# mic_array.net
KiCad netlist of a schematic drawn in Altium Designer
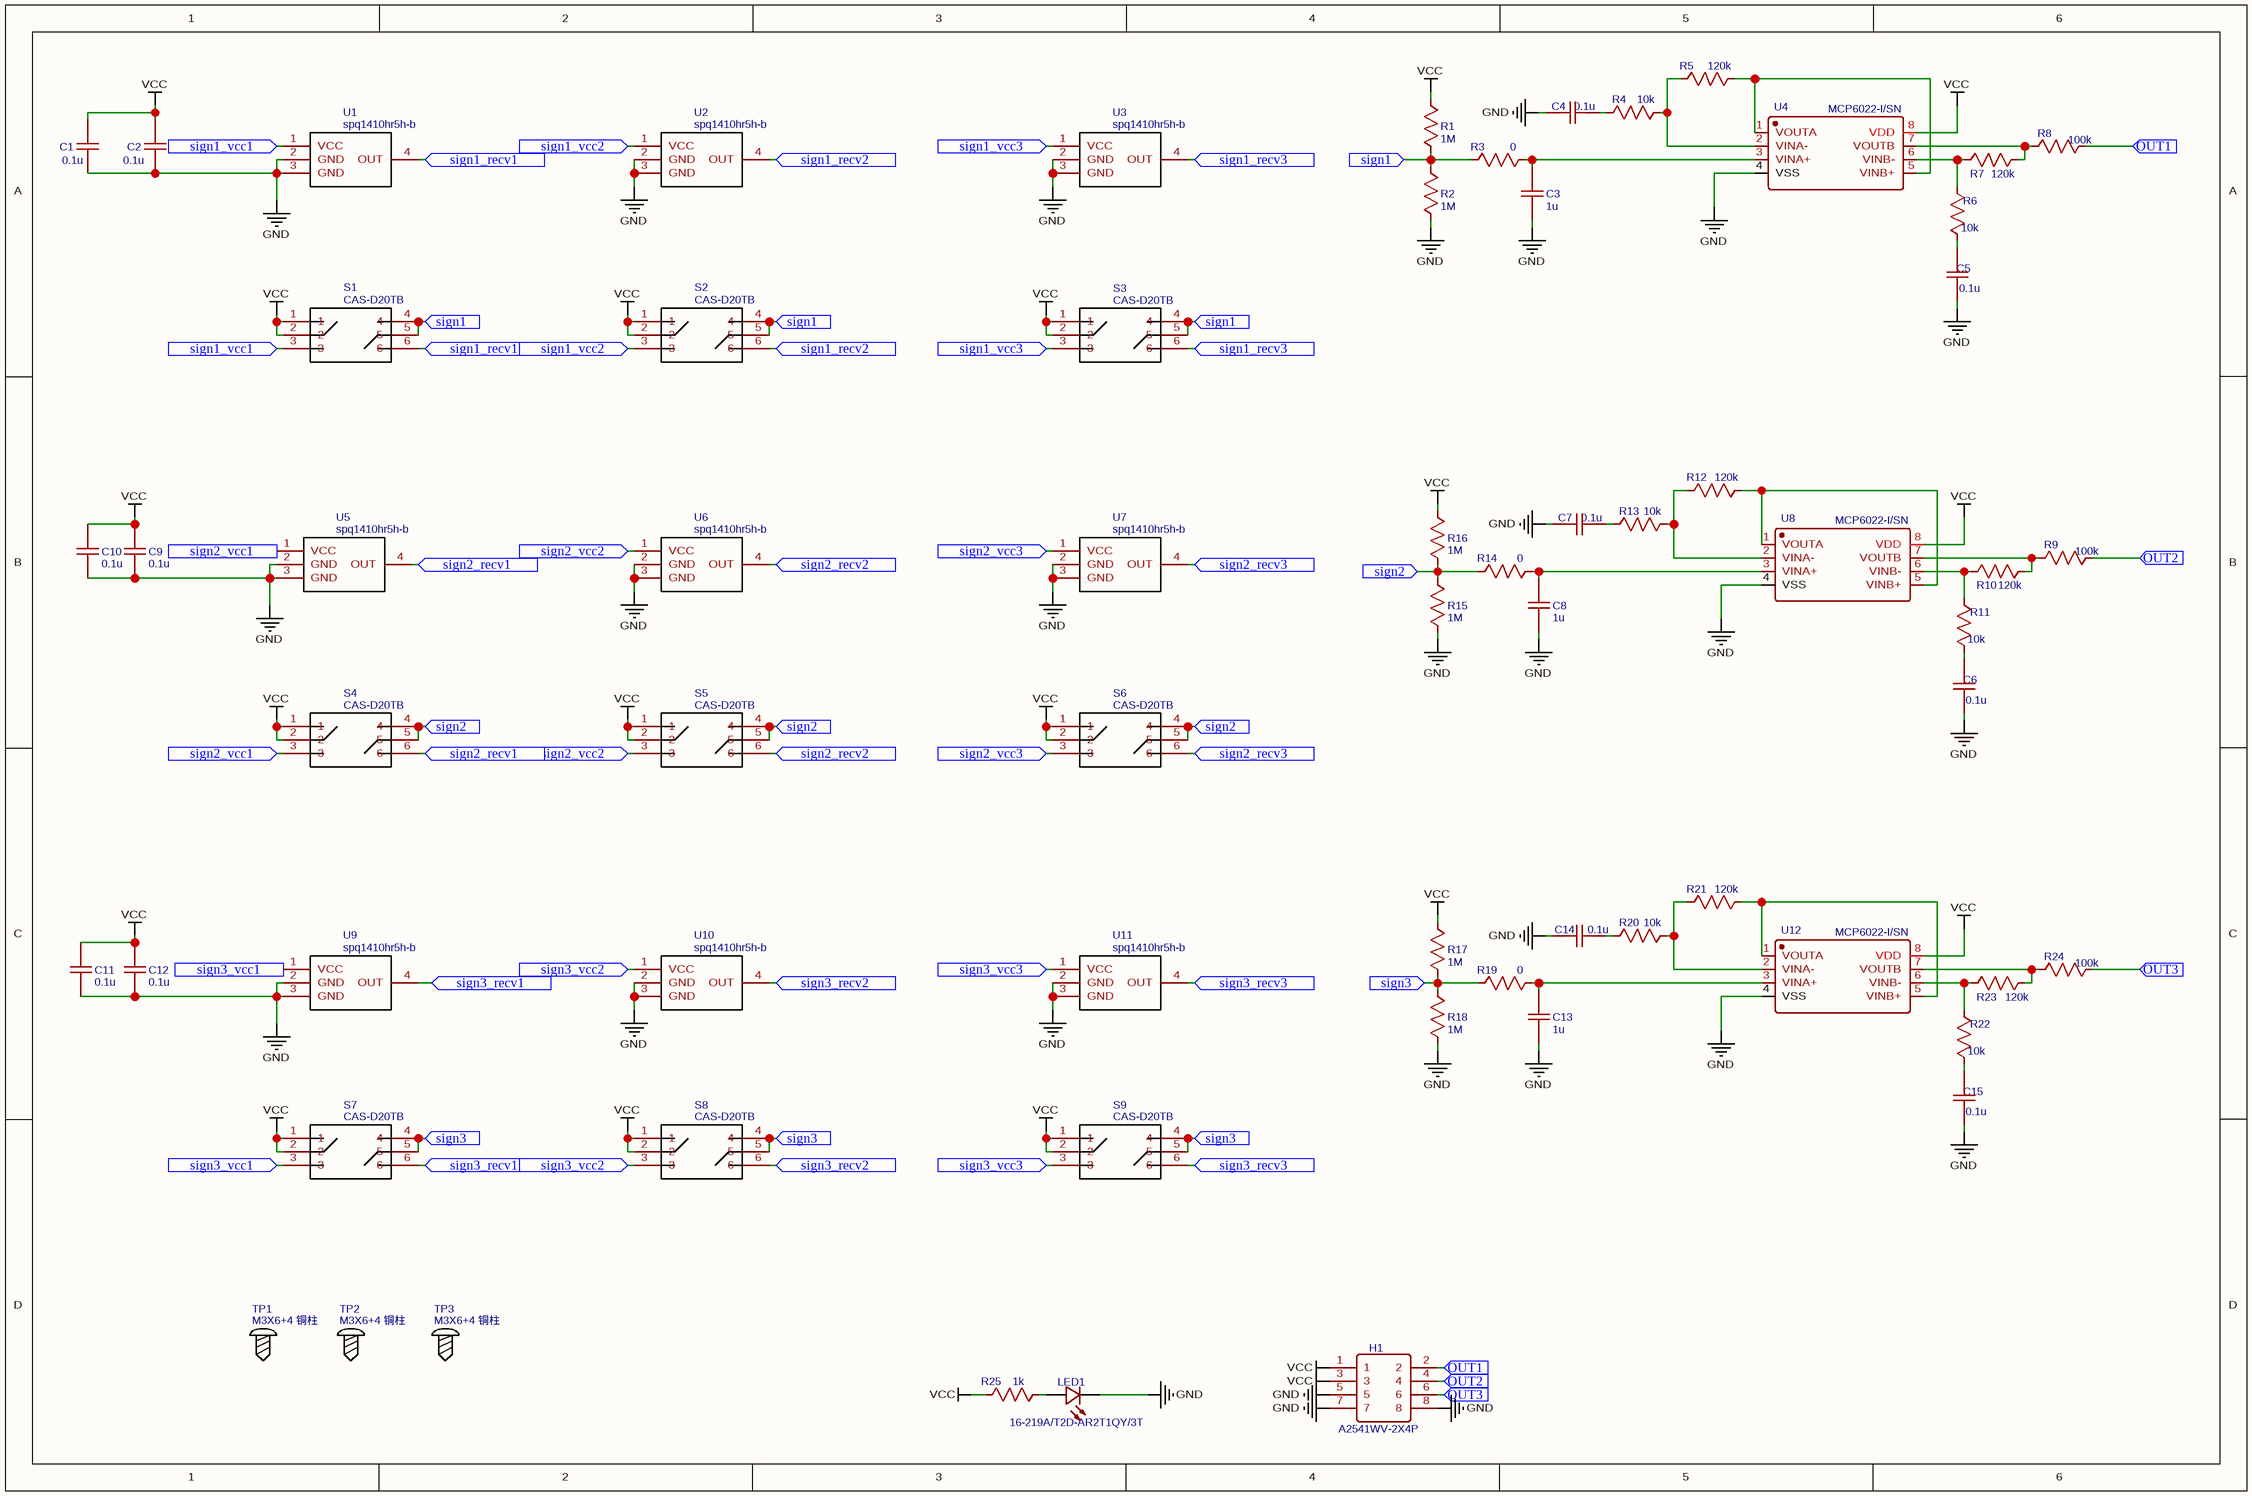
[diagram p0: mic_array.schdoc]

(export (version "E")
  (design (tool "Eeschema 10.0.6"))
  (components
    (comp (ref "C1")
      (value "0.1u")
      (fields (field (name "CONTRIBUTOR") "LCEDA_Lib"))
      (libsource (lib "altium-import") (part "root_1_0.1u_"))
    )
    (comp (ref "C2")
      (value "0.1u")
      (fields (field (name "CONTRIBUTOR") "LCEDA_Lib"))
      (libsource (lib "altium-import") (part "root_1_0.1u_"))
    )
    (comp (ref "C3")
      (value "1u")
      (fields (field (name "CONTRIBUTOR") "LCEDA_Lib"))
      (libsource (lib "altium-import") (part "root_1_1u_"))
    )
    (comp (ref "C4")
      (value "0.1u")
      (fields (field (name "CONTRIBUTOR") "LCEDA_Lib"))
      (libsource (lib "altium-import") (part "root_2_0.1u_"))
    )
    (comp (ref "C5")
      (value "0.1u")
      (fields (field (name "CONTRIBUTOR") "LCEDA_Lib"))
      (libsource (lib "altium-import") (part "root_1_0.1u_"))
    )
    (comp (ref "C6")
      (value "0.1u")
      (fields (field (name "CONTRIBUTOR") "LCEDA_Lib"))
      (libsource (lib "altium-import") (part "root_1_0.1u_"))
    )
    (comp (ref "C7")
      (value "0.1u")
      (fields (field (name "CONTRIBUTOR") "LCEDA_Lib"))
      (libsource (lib "altium-import") (part "root_2_0.1u_"))
    )
    (comp (ref "C8")
      (value "1u")
      (fields (field (name "CONTRIBUTOR") "LCEDA_Lib"))
      (libsource (lib "altium-import") (part "root_1_1u_"))
    )
    (comp (ref "C9")
      (value "0.1u")
      (fields (field (name "CONTRIBUTOR") "LCEDA_Lib"))
      (libsource (lib "altium-import") (part "root_1_0.1u_"))
    )
    (comp (ref "C10")
      (value "0.1u")
      (fields (field (name "CONTRIBUTOR") "LCEDA_Lib"))
      (libsource (lib "altium-import") (part "root_1_0.1u_"))
    )
    (comp (ref "C11")
      (value "0.1u")
      (fields (field (name "CONTRIBUTOR") "LCEDA_Lib"))
      (libsource (lib "altium-import") (part "root_1_0.1u_"))
    )
    (comp (ref "C12")
      (value "0.1u")
      (fields (field (name "CONTRIBUTOR") "LCEDA_Lib"))
      (libsource (lib "altium-import") (part "root_1_0.1u_"))
    )
    (comp (ref "C13")
      (value "1u")
      (fields (field (name "CONTRIBUTOR") "LCEDA_Lib"))
      (libsource (lib "altium-import") (part "root_1_1u_"))
    )
    (comp (ref "C14")
      (value "0.1u")
      (fields (field (name "CONTRIBUTOR") "LCEDA_Lib"))
      (libsource (lib "altium-import") (part "root_2_0.1u_"))
    )
    (comp (ref "C15")
      (value "0.1u")
      (fields (field (name "CONTRIBUTOR") "LCEDA_Lib"))
      (libsource (lib "altium-import") (part "root_1_0.1u_"))
    )
    (comp (ref "H1")
      (value "A2541WV-2X4P")
      (fields
        (field (name "BOM_SUPPLIER PART") "C225519")
        (field (name "BOM_MANUFACTURER PART") "A2541WV-2x4P")
        (field (name "CONTRIBUTOR") "LCSC")
      )
      (libsource (lib "altium-import") (part "root_0_A2541WV-2X4P_"))
    )
    (comp (ref "LED1")
      (value "16-219A/T2D-AR2T1QY/3T")
      (fields (field (name "BOM_SUPPLIER PART") "C74342"))
      (libsource (lib "altium-import") (part "root_2_16-219A/T2D-AR2T1QY/3T_"))
    )
    (comp (ref "R1")
      (value "1M")
      (fields (field (name "CONTRIBUTOR") "LCEDA_Lib"))
      (libsource (lib "altium-import") (part "root_1_1M_"))
    )
    (comp (ref "R2")
      (value "1M")
      (fields (field (name "CONTRIBUTOR") "LCEDA_Lib"))
      (libsource (lib "altium-import") (part "root_1_1M_"))
    )
    (comp (ref "R3")
      (value "0")
      (fields (field (name "CONTRIBUTOR") "LCEDA_Lib"))
      (libsource (lib "altium-import") (part "root_2_0_"))
    )
    (comp (ref "R4")
      (value "10k")
      (fields (field (name "CONTRIBUTOR") "LCEDA_Lib"))
      (libsource (lib "altium-import") (part "root_2_10k_"))
    )
    (comp (ref "R5")
      (value "120k")
      (fields (field (name "CONTRIBUTOR") "LCEDA_Lib"))
      (libsource (lib "altium-import") (part "root_2_120k_"))
    )
    (comp (ref "R6")
      (value "10k")
      (fields (field (name "CONTRIBUTOR") "LCEDA_Lib"))
      (libsource (lib "altium-import") (part "root_1_10k_"))
    )
    (comp (ref "R7")
      (value "120k")
      (fields (field (name "CONTRIBUTOR") "LCEDA_Lib"))
      (libsource (lib "altium-import") (part "root_2_120k_"))
    )
    (comp (ref "R8")
      (value "100k")
      (fields (field (name "CONTRIBUTOR") "LCEDA_Lib"))
      (libsource (lib "altium-import") (part "root_2_100k_"))
    )
    (comp (ref "R9")
      (value "100k")
      (fields (field (name "CONTRIBUTOR") "LCEDA_Lib"))
      (libsource (lib "altium-import") (part "root_2_100k_"))
    )
    (comp (ref "R10")
      (value "120k")
      (fields (field (name "CONTRIBUTOR") "LCEDA_Lib"))
      (libsource (lib "altium-import") (part "root_2_120k_"))
    )
    (comp (ref "R11")
      (value "10k")
      (fields (field (name "CONTRIBUTOR") "LCEDA_Lib"))
      (libsource (lib "altium-import") (part "root_1_10k_"))
    )
    (comp (ref "R12")
      (value "120k")
      (fields (field (name "CONTRIBUTOR") "LCEDA_Lib"))
      (libsource (lib "altium-import") (part "root_2_120k_"))
    )
    (comp (ref "R13")
      (value "10k")
      (fields (field (name "CONTRIBUTOR") "LCEDA_Lib"))
      (libsource (lib "altium-import") (part "root_2_10k_"))
    )
    (comp (ref "R14")
      (value "0")
      (fields (field (name "CONTRIBUTOR") "LCEDA_Lib"))
      (libsource (lib "altium-import") (part "root_2_0_"))
    )
    (comp (ref "R15")
      (value "1M")
      (fields (field (name "CONTRIBUTOR") "LCEDA_Lib"))
      (libsource (lib "altium-import") (part "root_1_1M_"))
    )
    (comp (ref "R16")
      (value "1M")
      (fields (field (name "CONTRIBUTOR") "LCEDA_Lib"))
      (libsource (lib "altium-import") (part "root_1_1M_"))
    )
    (comp (ref "R17")
      (value "1M")
      (fields (field (name "CONTRIBUTOR") "LCEDA_Lib"))
      (libsource (lib "altium-import") (part "root_1_1M_"))
    )
    (comp (ref "R18")
      (value "1M")
      (fields (field (name "CONTRIBUTOR") "LCEDA_Lib"))
      (libsource (lib "altium-import") (part "root_1_1M_"))
    )
    (comp (ref "R19")
      (value "0")
      (fields (field (name "CONTRIBUTOR") "LCEDA_Lib"))
      (libsource (lib "altium-import") (part "root_2_0_"))
    )
    (comp (ref "R20")
      (value "10k")
      (fields (field (name "CONTRIBUTOR") "LCEDA_Lib"))
      (libsource (lib "altium-import") (part "root_2_10k_"))
    )
    (comp (ref "R21")
      (value "120k")
      (fields (field (name "CONTRIBUTOR") "LCEDA_Lib"))
      (libsource (lib "altium-import") (part "root_2_120k_"))
    )
    (comp (ref "R22")
      (value "10k")
      (fields (field (name "CONTRIBUTOR") "LCEDA_Lib"))
      (libsource (lib "altium-import") (part "root_1_10k_"))
    )
    (comp (ref "R23")
      (value "120k")
      (fields (field (name "CONTRIBUTOR") "LCEDA_Lib"))
      (libsource (lib "altium-import") (part "root_2_120k_"))
    )
    (comp (ref "R24")
      (value "100k")
      (fields (field (name "CONTRIBUTOR") "LCEDA_Lib"))
      (libsource (lib "altium-import") (part "root_2_100k_"))
    )
    (comp (ref "R25")
      (value "1k")
      (fields (field (name "CONTRIBUTOR") "LCEDA_Lib"))
      (libsource (lib "altium-import") (part "root_0_1k_"))
    )
    (comp (ref "S1")
      (value "CAS-D20TB")
      (fields (field (name "CONTRIBUTOR") "iceeeewoo"))
      (libsource (lib "altium-import") (part "root_0_CAS-D20TB_"))
    )
    (comp (ref "S2")
      (value "CAS-D20TB")
      (fields (field (name "CONTRIBUTOR") "iceeeewoo"))
      (libsource (lib "altium-import") (part "root_0_CAS-D20TB_"))
    )
    (comp (ref "S3")
      (value "CAS-D20TB")
      (fields (field (name "CONTRIBUTOR") "iceeeewoo"))
      (libsource (lib "altium-import") (part "root_0_CAS-D20TB_"))
    )
    (comp (ref "S4")
      (value "CAS-D20TB")
      (fields (field (name "CONTRIBUTOR") "iceeeewoo"))
      (libsource (lib "altium-import") (part "root_0_CAS-D20TB_"))
    )
    (comp (ref "S5")
      (value "CAS-D20TB")
      (fields (field (name "CONTRIBUTOR") "iceeeewoo"))
      (libsource (lib "altium-import") (part "root_0_CAS-D20TB_"))
    )
    (comp (ref "S6")
      (value "CAS-D20TB")
      (fields (field (name "CONTRIBUTOR") "iceeeewoo"))
      (libsource (lib "altium-import") (part "root_0_CAS-D20TB_"))
    )
    (comp (ref "S7")
      (value "CAS-D20TB")
      (fields (field (name "CONTRIBUTOR") "iceeeewoo"))
      (libsource (lib "altium-import") (part "root_0_CAS-D20TB_"))
    )
    (comp (ref "S8")
      (value "CAS-D20TB")
      (fields (field (name "CONTRIBUTOR") "iceeeewoo"))
      (libsource (lib "altium-import") (part "root_0_CAS-D20TB_"))
    )
    (comp (ref "S9")
      (value "CAS-D20TB")
      (fields (field (name "CONTRIBUTOR") "iceeeewoo"))
      (libsource (lib "altium-import") (part "root_0_CAS-D20TB_"))
    )
    (comp (ref "TP1")
      (value "M3X6+4 铜柱")
      (fields (field (name "BOM_SUPPLIER PART") "C551320") (field (name "CONTRIBUTOR") "eda2022"))
      (libsource (lib "altium-import") (part "root_0_M3X6+4 铜柱_"))
    )
    (comp (ref "TP2")
      (value "M3X6+4 铜柱")
      (fields (field (name "BOM_SUPPLIER PART") "C551320") (field (name "CONTRIBUTOR") "eda2022"))
      (libsource (lib "altium-import") (part "root_0_M3X6+4 铜柱_"))
    )
    (comp (ref "TP3")
      (value "M3X6+4 铜柱")
      (fields (field (name "BOM_SUPPLIER PART") "C551320") (field (name "CONTRIBUTOR") "eda2022"))
      (libsource (lib "altium-import") (part "root_0_M3X6+4 铜柱_"))
    )
    (comp (ref "U1")
      (value "spq1410hr5h-b")
      (fields (field (name "CONTRIBUTOR") "Iceeeewoo"))
      (libsource (lib "altium-import") (part "root_0_spq1410hr5h-b_"))
    )
    (comp (ref "U2")
      (value "spq1410hr5h-b")
      (fields (field (name "CONTRIBUTOR") "Iceeeewoo"))
      (libsource (lib "altium-import") (part "root_0_spq1410hr5h-b_"))
    )
    (comp (ref "U3")
      (value "spq1410hr5h-b")
      (fields (field (name "CONTRIBUTOR") "Iceeeewoo"))
      (libsource (lib "altium-import") (part "root_0_spq1410hr5h-b_"))
    )
    (comp (ref "U4")
      (value "MCP6022-I/SN")
      (fields (field (name "BOM_SUPPLIER PART") "C34047"))
      (libsource (lib "altium-import") (part "root_0_MCP6022-I/SN_"))
    )
    (comp (ref "U5")
      (value "spq1410hr5h-b")
      (fields (field (name "CONTRIBUTOR") "Iceeeewoo"))
      (libsource (lib "altium-import") (part "root_0_spq1410hr5h-b_"))
    )
    (comp (ref "U6")
      (value "spq1410hr5h-b")
      (fields (field (name "CONTRIBUTOR") "Iceeeewoo"))
      (libsource (lib "altium-import") (part "root_0_spq1410hr5h-b_"))
    )
    (comp (ref "U7")
      (value "spq1410hr5h-b")
      (fields (field (name "CONTRIBUTOR") "Iceeeewoo"))
      (libsource (lib "altium-import") (part "root_0_spq1410hr5h-b_"))
    )
    (comp (ref "U8")
      (value "MCP6022-I/SN")
      (fields (field (name "BOM_SUPPLIER PART") "C34047"))
      (libsource (lib "altium-import") (part "root_0_MCP6022-I/SN_"))
    )
    (comp (ref "U9")
      (value "spq1410hr5h-b")
      (fields (field (name "CONTRIBUTOR") "Iceeeewoo"))
      (libsource (lib "altium-import") (part "root_0_spq1410hr5h-b_"))
    )
    (comp (ref "U10")
      (value "spq1410hr5h-b")
      (fields (field (name "CONTRIBUTOR") "Iceeeewoo"))
      (libsource (lib "altium-import") (part "root_0_spq1410hr5h-b_"))
    )
    (comp (ref "U11")
      (value "spq1410hr5h-b")
      (fields (field (name "CONTRIBUTOR") "Iceeeewoo"))
      (libsource (lib "altium-import") (part "root_0_spq1410hr5h-b_"))
    )
    (comp (ref "U12")
      (value "MCP6022-I/SN")
      (fields (field (name "BOM_SUPPLIER PART") "C34047"))
      (libsource (lib "altium-import") (part "root_0_MCP6022-I/SN_"))
    )
  )
  (nets
    (net (code "1") (name "/OUT1") (class "Default")
      (node (ref "H1") (pin "2") (pinfunction "2_2") (pintype "passive"))
      (node (ref "R8") (pin "1") (pinfunction "1_1") (pintype "passive"))
    )
    (net (code "2") (name "/OUT2") (class "Default")
      (node (ref "H1") (pin "4") (pinfunction "4_4") (pintype "passive"))
      (node (ref "R9") (pin "1") (pinfunction "1_1") (pintype "passive"))
    )
    (net (code "3") (name "/OUT3") (class "Default")
      (node (ref "H1") (pin "6") (pinfunction "6_6") (pintype "passive"))
      (node (ref "R24") (pin "1") (pinfunction "1_1") (pintype "passive"))
    )
    (net (code "4") (name "/sign1") (class "Default")
      (node (ref "R1") (pin "1") (pinfunction "1_1") (pintype "passive"))
      (node (ref "R2") (pin "2") (pinfunction "2_2") (pintype "passive"))
      (node (ref "R3") (pin "2") (pinfunction "2_2") (pintype "passive"))
      (node (ref "S1") (pin "4") (pinfunction "4_4") (pintype "passive"))
      (node (ref "S1") (pin "5") (pinfunction "5_5") (pintype "passive"))
      (node (ref "S2") (pin "4") (pinfunction "4_4") (pintype "passive"))
      (node (ref "S2") (pin "5") (pinfunction "5_5") (pintype "passive"))
      (node (ref "S3") (pin "4") (pinfunction "4_4") (pintype "passive"))
      (node (ref "S3") (pin "5") (pinfunction "5_5") (pintype "passive"))
    )
    (net (code "5") (name "/sign1_recv1") (class "Default")
      (node (ref "S1") (pin "6") (pinfunction "6_6") (pintype "passive"))
      (node (ref "U1") (pin "4") (pinfunction "OUT_4") (pintype "passive"))
    )
    (net (code "6") (name "/sign1_recv2") (class "Default")
      (node (ref "S2") (pin "6") (pinfunction "6_6") (pintype "passive"))
      (node (ref "U2") (pin "4") (pinfunction "OUT_4") (pintype "passive"))
    )
    (net (code "7") (name "/sign1_recv3") (class "Default")
      (node (ref "S3") (pin "6") (pinfunction "6_6") (pintype "passive"))
      (node (ref "U3") (pin "4") (pinfunction "OUT_4") (pintype "passive"))
    )
    (net (code "8") (name "/sign1_vcc1") (class "Default")
      (node (ref "S1") (pin "3") (pinfunction "3_3") (pintype "passive"))
      (node (ref "U1") (pin "1") (pinfunction "VCC_1") (pintype "passive"))
    )
    (net (code "9") (name "/sign1_vcc2") (class "Default")
      (node (ref "S2") (pin "3") (pinfunction "3_3") (pintype "passive"))
      (node (ref "U2") (pin "1") (pinfunction "VCC_1") (pintype "passive"))
    )
    (net (code "10") (name "/sign1_vcc3") (class "Default")
      (node (ref "S3") (pin "3") (pinfunction "3_3") (pintype "passive"))
      (node (ref "U3") (pin "1") (pinfunction "VCC_1") (pintype "passive"))
    )
    (net (code "11") (name "/sign2") (class "Default")
      (node (ref "R14") (pin "2") (pinfunction "2_2") (pintype "passive"))
      (node (ref "R15") (pin "2") (pinfunction "2_2") (pintype "passive"))
      (node (ref "R16") (pin "1") (pinfunction "1_1") (pintype "passive"))
      (node (ref "S4") (pin "4") (pinfunction "4_4") (pintype "passive"))
      (node (ref "S4") (pin "5") (pinfunction "5_5") (pintype "passive"))
      (node (ref "S5") (pin "4") (pinfunction "4_4") (pintype "passive"))
      (node (ref "S5") (pin "5") (pinfunction "5_5") (pintype "passive"))
      (node (ref "S6") (pin "4") (pinfunction "4_4") (pintype "passive"))
      (node (ref "S6") (pin "5") (pinfunction "5_5") (pintype "passive"))
    )
    (net (code "12") (name "/sign2_recv1") (class "Default")
      (node (ref "S4") (pin "6") (pinfunction "6_6") (pintype "passive"))
      (node (ref "U5") (pin "4") (pinfunction "OUT_4") (pintype "passive"))
    )
    (net (code "13") (name "/sign2_recv2") (class "Default")
      (node (ref "S5") (pin "6") (pinfunction "6_6") (pintype "passive"))
      (node (ref "U6") (pin "4") (pinfunction "OUT_4") (pintype "passive"))
    )
    (net (code "14") (name "/sign2_recv3") (class "Default")
      (node (ref "S6") (pin "6") (pinfunction "6_6") (pintype "passive"))
      (node (ref "U7") (pin "4") (pinfunction "OUT_4") (pintype "passive"))
    )
    (net (code "15") (name "/sign2_vcc1") (class "Default")
      (node (ref "S4") (pin "3") (pinfunction "3_3") (pintype "passive"))
      (node (ref "U5") (pin "1") (pinfunction "VCC_1") (pintype "passive"))
    )
    (net (code "16") (name "/sign2_vcc2") (class "Default")
      (node (ref "S5") (pin "3") (pinfunction "3_3") (pintype "passive"))
      (node (ref "U6") (pin "1") (pinfunction "VCC_1") (pintype "passive"))
    )
    (net (code "17") (name "/sign2_vcc3") (class "Default")
      (node (ref "S6") (pin "3") (pinfunction "3_3") (pintype "passive"))
      (node (ref "U7") (pin "1") (pinfunction "VCC_1") (pintype "passive"))
    )
    (net (code "18") (name "/sign3") (class "Default")
      (node (ref "R17") (pin "1") (pinfunction "1_1") (pintype "passive"))
      (node (ref "R18") (pin "2") (pinfunction "2_2") (pintype "passive"))
      (node (ref "R19") (pin "2") (pinfunction "2_2") (pintype "passive"))
      (node (ref "S7") (pin "4") (pinfunction "4_4") (pintype "passive"))
      (node (ref "S7") (pin "5") (pinfunction "5_5") (pintype "passive"))
      (node (ref "S8") (pin "4") (pinfunction "4_4") (pintype "passive"))
      (node (ref "S8") (pin "5") (pinfunction "5_5") (pintype "passive"))
      (node (ref "S9") (pin "4") (pinfunction "4_4") (pintype "passive"))
      (node (ref "S9") (pin "5") (pinfunction "5_5") (pintype "passive"))
    )
    (net (code "19") (name "/sign3_recv1") (class "Default")
      (node (ref "S7") (pin "6") (pinfunction "6_6") (pintype "passive"))
      (node (ref "U9") (pin "4") (pinfunction "OUT_4") (pintype "passive"))
    )
    (net (code "20") (name "/sign3_recv2") (class "Default")
      (node (ref "S8") (pin "6") (pinfunction "6_6") (pintype "passive"))
      (node (ref "U10") (pin "4") (pinfunction "OUT_4") (pintype "passive"))
    )
    (net (code "21") (name "/sign3_recv3") (class "Default")
      (node (ref "S9") (pin "6") (pinfunction "6_6") (pintype "passive"))
      (node (ref "U11") (pin "4") (pinfunction "OUT_4") (pintype "passive"))
    )
    (net (code "22") (name "/sign3_vcc1") (class "Default")
      (node (ref "S7") (pin "3") (pinfunction "3_3") (pintype "passive"))
      (node (ref "U9") (pin "1") (pinfunction "VCC_1") (pintype "passive"))
    )
    (net (code "23") (name "/sign3_vcc2") (class "Default")
      (node (ref "S8") (pin "3") (pinfunction "3_3") (pintype "passive"))
      (node (ref "U10") (pin "1") (pinfunction "VCC_1") (pintype "passive"))
    )
    (net (code "24") (name "/sign3_vcc3") (class "Default")
      (node (ref "S9") (pin "3") (pinfunction "3_3") (pintype "passive"))
      (node (ref "U11") (pin "1") (pinfunction "VCC_1") (pintype "passive"))
    )
    (net (code "25") (name "GND") (class "Default")
      (node (ref "C1") (pin "1") (pinfunction "1_1") (pintype "passive"))
      (node (ref "C10") (pin "1") (pinfunction "1_1") (pintype "passive"))
      (node (ref "C11") (pin "1") (pinfunction "1_1") (pintype "passive"))
      (node (ref "C12") (pin "1") (pinfunction "1_1") (pintype "passive"))
      (node (ref "C13") (pin "1") (pinfunction "1_1") (pintype "passive"))
      (node (ref "C14") (pin "2") (pinfunction "2_2") (pintype "passive"))
      (node (ref "C15") (pin "1") (pinfunction "1_1") (pintype "passive"))
      (node (ref "C2") (pin "1") (pinfunction "1_1") (pintype "passive"))
      (node (ref "C3") (pin "1") (pinfunction "1_1") (pintype "passive"))
      (node (ref "C4") (pin "2") (pinfunction "2_2") (pintype "passive"))
      (node (ref "C5") (pin "1") (pinfunction "1_1") (pintype "passive"))
      (node (ref "C6") (pin "1") (pinfunction "1_1") (pintype "passive"))
      (node (ref "C7") (pin "2") (pinfunction "2_2") (pintype "passive"))
      (node (ref "C8") (pin "1") (pinfunction "1_1") (pintype "passive"))
      (node (ref "C9") (pin "1") (pinfunction "1_1") (pintype "passive"))
      (node (ref "H1") (pin "5") (pinfunction "5_5") (pintype "passive"))
      (node (ref "H1") (pin "7") (pinfunction "7_7") (pintype "passive"))
      (node (ref "H1") (pin "8") (pinfunction "8_8") (pintype "passive"))
      (node (ref "LED1") (pin "1") (pinfunction "-_1") (pintype "passive"))
      (node (ref "R15") (pin "1") (pinfunction "1_1") (pintype "passive"))
      (node (ref "R18") (pin "1") (pinfunction "1_1") (pintype "passive"))
      (node (ref "R2") (pin "1") (pinfunction "1_1") (pintype "passive"))
      (node (ref "U1") (pin "2") (pinfunction "GND_2") (pintype "passive"))
      (node (ref "U1") (pin "3") (pinfunction "GND_3") (pintype "passive"))
      (node (ref "U10") (pin "2") (pinfunction "GND_2") (pintype "passive"))
      (node (ref "U10") (pin "3") (pinfunction "GND_3") (pintype "passive"))
      (node (ref "U11") (pin "2") (pinfunction "GND_2") (pintype "passive"))
      (node (ref "U11") (pin "3") (pinfunction "GND_3") (pintype "passive"))
      (node (ref "U12") (pin "4") (pinfunction "VSS_4") (pintype "passive"))
      (node (ref "U2") (pin "2") (pinfunction "GND_2") (pintype "passive"))
      (node (ref "U2") (pin "3") (pinfunction "GND_3") (pintype "passive"))
      (node (ref "U3") (pin "2") (pinfunction "GND_2") (pintype "passive"))
      (node (ref "U3") (pin "3") (pinfunction "GND_3") (pintype "passive"))
      (node (ref "U4") (pin "4") (pinfunction "VSS_4") (pintype "passive"))
      (node (ref "U5") (pin "2") (pinfunction "GND_2") (pintype "passive"))
      (node (ref "U5") (pin "3") (pinfunction "GND_3") (pintype "passive"))
      (node (ref "U6") (pin "2") (pinfunction "GND_2") (pintype "passive"))
      (node (ref "U6") (pin "3") (pinfunction "GND_3") (pintype "passive"))
      (node (ref "U7") (pin "2") (pinfunction "GND_2") (pintype "passive"))
      (node (ref "U7") (pin "3") (pinfunction "GND_3") (pintype "passive"))
      (node (ref "U8") (pin "4") (pinfunction "VSS_4") (pintype "passive"))
      (node (ref "U9") (pin "2") (pinfunction "GND_2") (pintype "passive"))
      (node (ref "U9") (pin "3") (pinfunction "GND_3") (pintype "passive"))
    )
    (net (code "26") (name "Net-(C4-Pad1)") (class "Default")
      (node (ref "C4") (pin "1") (pinfunction "1_1") (pintype "passive"))
      (node (ref "R4") (pin "2") (pinfunction "2_2") (pintype "passive"))
    )
    (net (code "27") (name "Net-(C5-Pad2)") (class "Default")
      (node (ref "C5") (pin "2") (pinfunction "2_2") (pintype "passive"))
      (node (ref "R6") (pin "1") (pinfunction "1_1") (pintype "passive"))
    )
    (net (code "28") (name "Net-(C6-Pad2)") (class "Default")
      (node (ref "C6") (pin "2") (pinfunction "2_2") (pintype "passive"))
      (node (ref "R11") (pin "1") (pinfunction "1_1") (pintype "passive"))
    )
    (net (code "29") (name "Net-(C7-Pad1)") (class "Default")
      (node (ref "C7") (pin "1") (pinfunction "1_1") (pintype "passive"))
      (node (ref "R13") (pin "2") (pinfunction "2_2") (pintype "passive"))
    )
    (net (code "30") (name "Net-(C14-Pad1)") (class "Default")
      (node (ref "C14") (pin "1") (pinfunction "1_1") (pintype "passive"))
      (node (ref "R20") (pin "2") (pinfunction "2_2") (pintype "passive"))
    )
    (net (code "31") (name "Net-(C15-Pad2)") (class "Default")
      (node (ref "C15") (pin "2") (pinfunction "2_2") (pintype "passive"))
      (node (ref "R22") (pin "1") (pinfunction "1_1") (pintype "passive"))
    )
    (net (code "32") (name "Net-(LED1-+)") (class "Default")
      (node (ref "LED1") (pin "2") (pinfunction "+_2") (pintype "passive"))
      (node (ref "R25") (pin "2") (pinfunction "2_2") (pintype "passive"))
    )
    (net (code "33") (name "Net-(U4-VINA+)") (class "Default")
      (node (ref "C3") (pin "2") (pinfunction "2_2") (pintype "passive"))
      (node (ref "R3") (pin "1") (pinfunction "1_1") (pintype "passive"))
      (node (ref "U4") (pin "3") (pinfunction "VINA+_3") (pintype "passive"))
    )
    (net (code "34") (name "Net-(U4-VINA-)") (class "Default")
      (node (ref "R4") (pin "1") (pinfunction "1_1") (pintype "passive"))
      (node (ref "R5") (pin "2") (pinfunction "2_2") (pintype "passive"))
      (node (ref "U4") (pin "2") (pinfunction "VINA-_2") (pintype "passive"))
    )
    (net (code "35") (name "Net-(U4-VINB+)") (class "Default")
      (node (ref "R5") (pin "1") (pinfunction "1_1") (pintype "passive"))
      (node (ref "U4") (pin "1") (pinfunction "VOUTA_1") (pintype "passive"))
      (node (ref "U4") (pin "5") (pinfunction "VINB+_5") (pintype "passive"))
    )
    (net (code "36") (name "Net-(U4-VINB-)") (class "Default")
      (node (ref "R6") (pin "2") (pinfunction "2_2") (pintype "passive"))
      (node (ref "R7") (pin "2") (pinfunction "2_2") (pintype "passive"))
      (node (ref "U4") (pin "6") (pinfunction "VINB-_6") (pintype "passive"))
    )
    (net (code "37") (name "Net-(U4-VOUTB)") (class "Default")
      (node (ref "R7") (pin "1") (pinfunction "1_1") (pintype "passive"))
      (node (ref "R8") (pin "2") (pinfunction "2_2") (pintype "passive"))
      (node (ref "U4") (pin "7") (pinfunction "VOUTB_7") (pintype "passive"))
    )
    (net (code "38") (name "Net-(U8-VINA+)") (class "Default")
      (node (ref "C8") (pin "2") (pinfunction "2_2") (pintype "passive"))
      (node (ref "R14") (pin "1") (pinfunction "1_1") (pintype "passive"))
      (node (ref "U8") (pin "3") (pinfunction "VINA+_3") (pintype "passive"))
    )
    (net (code "39") (name "Net-(U8-VINA-)") (class "Default")
      (node (ref "R12") (pin "2") (pinfunction "2_2") (pintype "passive"))
      (node (ref "R13") (pin "1") (pinfunction "1_1") (pintype "passive"))
      (node (ref "U8") (pin "2") (pinfunction "VINA-_2") (pintype "passive"))
    )
    (net (code "40") (name "Net-(U8-VINB+)") (class "Default")
      (node (ref "R12") (pin "1") (pinfunction "1_1") (pintype "passive"))
      (node (ref "U8") (pin "1") (pinfunction "VOUTA_1") (pintype "passive"))
      (node (ref "U8") (pin "5") (pinfunction "VINB+_5") (pintype "passive"))
    )
    (net (code "41") (name "Net-(U8-VINB-)") (class "Default")
      (node (ref "R10") (pin "2") (pinfunction "2_2") (pintype "passive"))
      (node (ref "R11") (pin "2") (pinfunction "2_2") (pintype "passive"))
      (node (ref "U8") (pin "6") (pinfunction "VINB-_6") (pintype "passive"))
    )
    (net (code "42") (name "Net-(U8-VOUTB)") (class "Default")
      (node (ref "R10") (pin "1") (pinfunction "1_1") (pintype "passive"))
      (node (ref "R9") (pin "2") (pinfunction "2_2") (pintype "passive"))
      (node (ref "U8") (pin "7") (pinfunction "VOUTB_7") (pintype "passive"))
    )
    (net (code "43") (name "Net-(U12-VINA+)") (class "Default")
      (node (ref "C13") (pin "2") (pinfunction "2_2") (pintype "passive"))
      (node (ref "R19") (pin "1") (pinfunction "1_1") (pintype "passive"))
      (node (ref "U12") (pin "3") (pinfunction "VINA+_3") (pintype "passive"))
    )
    (net (code "44") (name "Net-(U12-VINA-)") (class "Default")
      (node (ref "R20") (pin "1") (pinfunction "1_1") (pintype "passive"))
      (node (ref "R21") (pin "2") (pinfunction "2_2") (pintype "passive"))
      (node (ref "U12") (pin "2") (pinfunction "VINA-_2") (pintype "passive"))
    )
    (net (code "45") (name "Net-(U12-VINB+)") (class "Default")
      (node (ref "R21") (pin "1") (pinfunction "1_1") (pintype "passive"))
      (node (ref "U12") (pin "1") (pinfunction "VOUTA_1") (pintype "passive"))
      (node (ref "U12") (pin "5") (pinfunction "VINB+_5") (pintype "passive"))
    )
    (net (code "46") (name "Net-(U12-VINB-)") (class "Default")
      (node (ref "R22") (pin "2") (pinfunction "2_2") (pintype "passive"))
      (node (ref "R23") (pin "2") (pinfunction "2_2") (pintype "passive"))
      (node (ref "U12") (pin "6") (pinfunction "VINB-_6") (pintype "passive"))
    )
    (net (code "47") (name "Net-(U12-VOUTB)") (class "Default")
      (node (ref "R23") (pin "1") (pinfunction "1_1") (pintype "passive"))
      (node (ref "R24") (pin "2") (pinfunction "2_2") (pintype "passive"))
      (node (ref "U12") (pin "7") (pinfunction "VOUTB_7") (pintype "passive"))
    )
    (net (code "48") (name "VCC") (class "Default")
      (node (ref "C1") (pin "2") (pinfunction "2_2") (pintype "passive"))
      (node (ref "C10") (pin "2") (pinfunction "2_2") (pintype "passive"))
      (node (ref "C11") (pin "2") (pinfunction "2_2") (pintype "passive"))
      (node (ref "C12") (pin "2") (pinfunction "2_2") (pintype "passive"))
      (node (ref "C2") (pin "2") (pinfunction "2_2") (pintype "passive"))
      (node (ref "C9") (pin "2") (pinfunction "2_2") (pintype "passive"))
      (node (ref "H1") (pin "1") (pinfunction "1_1") (pintype "passive"))
      (node (ref "H1") (pin "3") (pinfunction "3_3") (pintype "passive"))
      (node (ref "R1") (pin "2") (pinfunction "2_2") (pintype "passive"))
      (node (ref "R16") (pin "2") (pinfunction "2_2") (pintype "passive"))
      (node (ref "R17") (pin "2") (pinfunction "2_2") (pintype "passive"))
      (node (ref "R25") (pin "1") (pinfunction "1_1") (pintype "passive"))
      (node (ref "S1") (pin "1") (pinfunction "1_1") (pintype "passive"))
      (node (ref "S1") (pin "2") (pinfunction "2_2") (pintype "passive"))
      (node (ref "S2") (pin "1") (pinfunction "1_1") (pintype "passive"))
      (node (ref "S2") (pin "2") (pinfunction "2_2") (pintype "passive"))
      (node (ref "S3") (pin "1") (pinfunction "1_1") (pintype "passive"))
      (node (ref "S3") (pin "2") (pinfunction "2_2") (pintype "passive"))
      (node (ref "S4") (pin "1") (pinfunction "1_1") (pintype "passive"))
      (node (ref "S4") (pin "2") (pinfunction "2_2") (pintype "passive"))
      (node (ref "S5") (pin "1") (pinfunction "1_1") (pintype "passive"))
      (node (ref "S5") (pin "2") (pinfunction "2_2") (pintype "passive"))
      (node (ref "S6") (pin "1") (pinfunction "1_1") (pintype "passive"))
      (node (ref "S6") (pin "2") (pinfunction "2_2") (pintype "passive"))
      (node (ref "S7") (pin "1") (pinfunction "1_1") (pintype "passive"))
      (node (ref "S7") (pin "2") (pinfunction "2_2") (pintype "passive"))
      (node (ref "S8") (pin "1") (pinfunction "1_1") (pintype "passive"))
      (node (ref "S8") (pin "2") (pinfunction "2_2") (pintype "passive"))
      (node (ref "S9") (pin "1") (pinfunction "1_1") (pintype "passive"))
      (node (ref "S9") (pin "2") (pinfunction "2_2") (pintype "passive"))
      (node (ref "U12") (pin "8") (pinfunction "VDD_8") (pintype "passive"))
      (node (ref "U4") (pin "8") (pinfunction "VDD_8") (pintype "passive"))
      (node (ref "U8") (pin "8") (pinfunction "VDD_8") (pintype "passive"))
    )
  )
)
